# PROCESSOR.net
KiCad netlist of a schematic drawn in Altium Designer
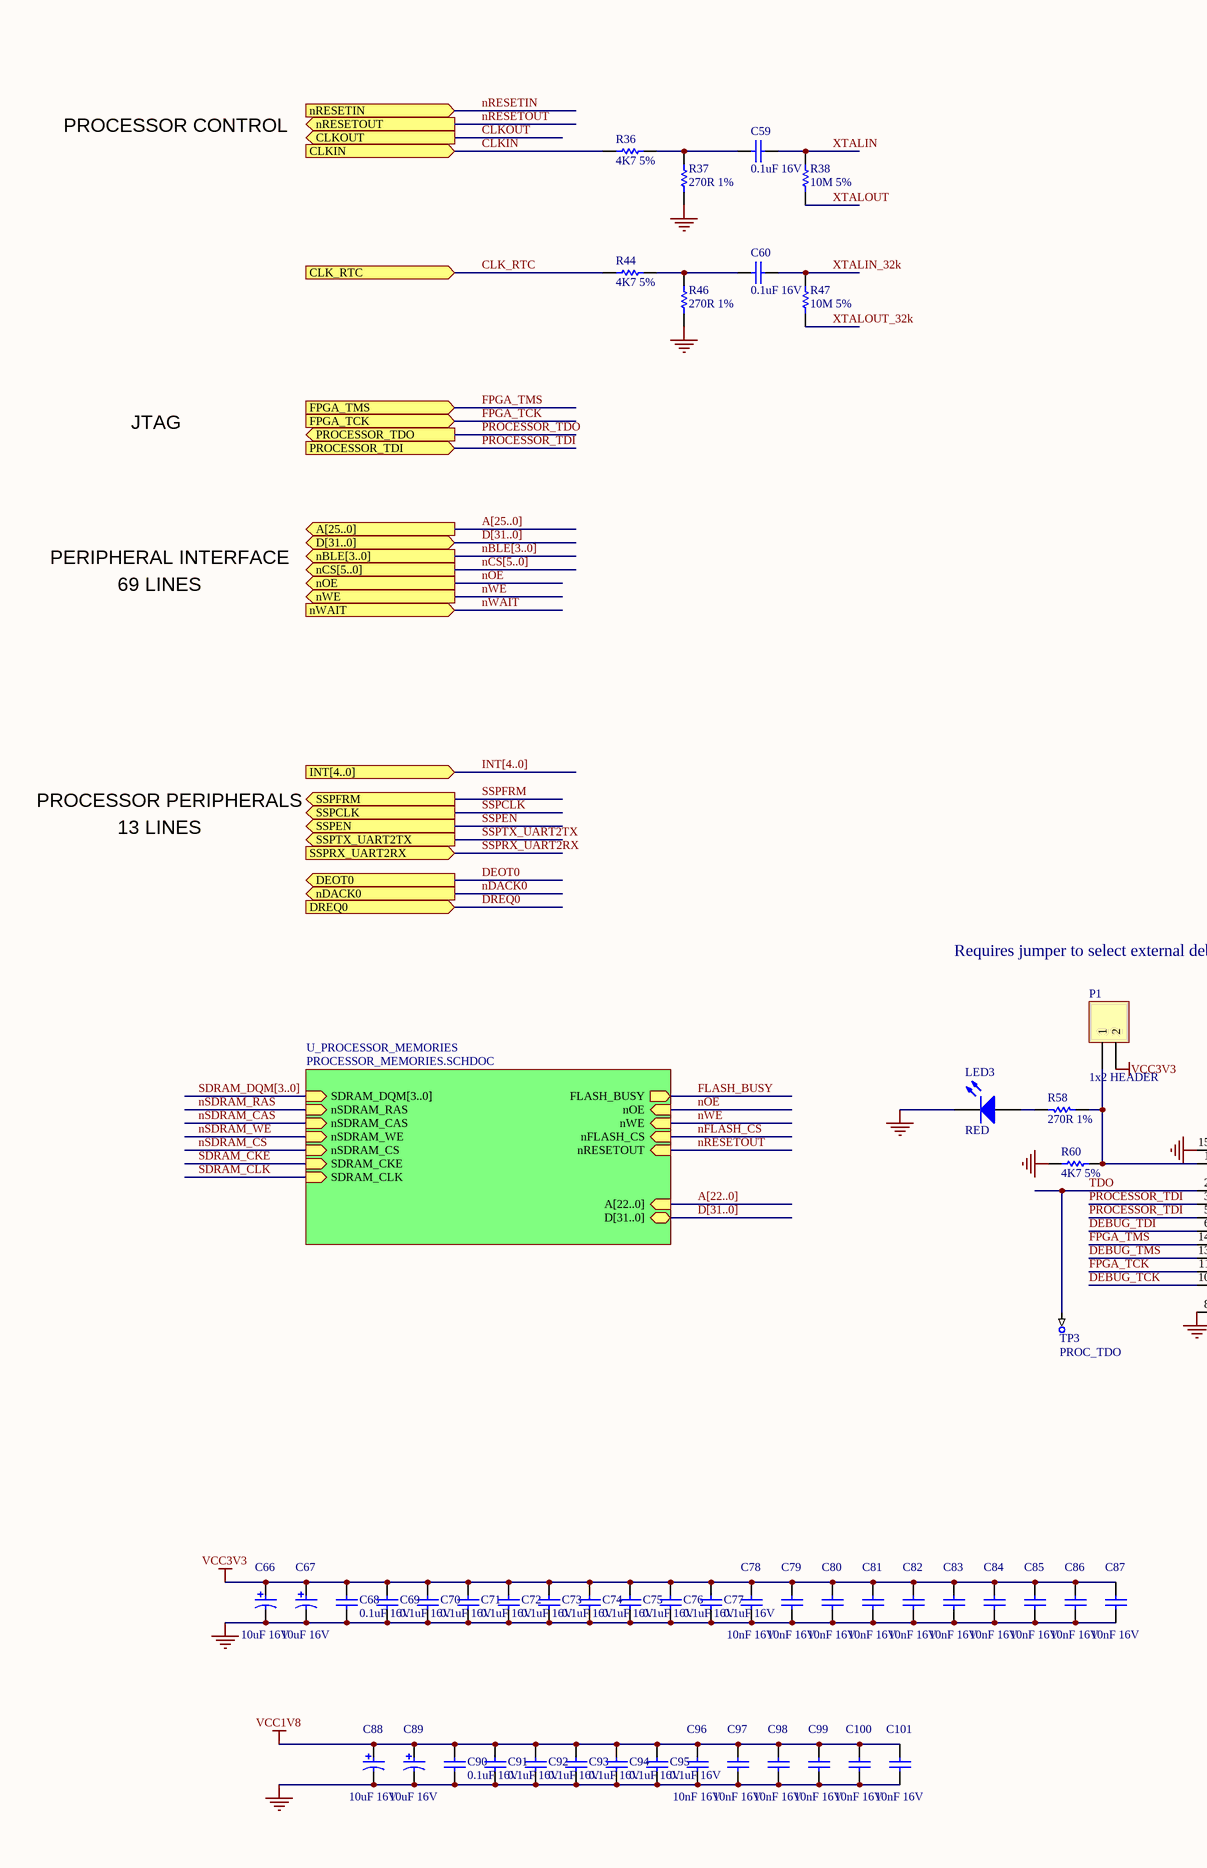
[diagram p0: PROCESSOR.SCHDOC, left]
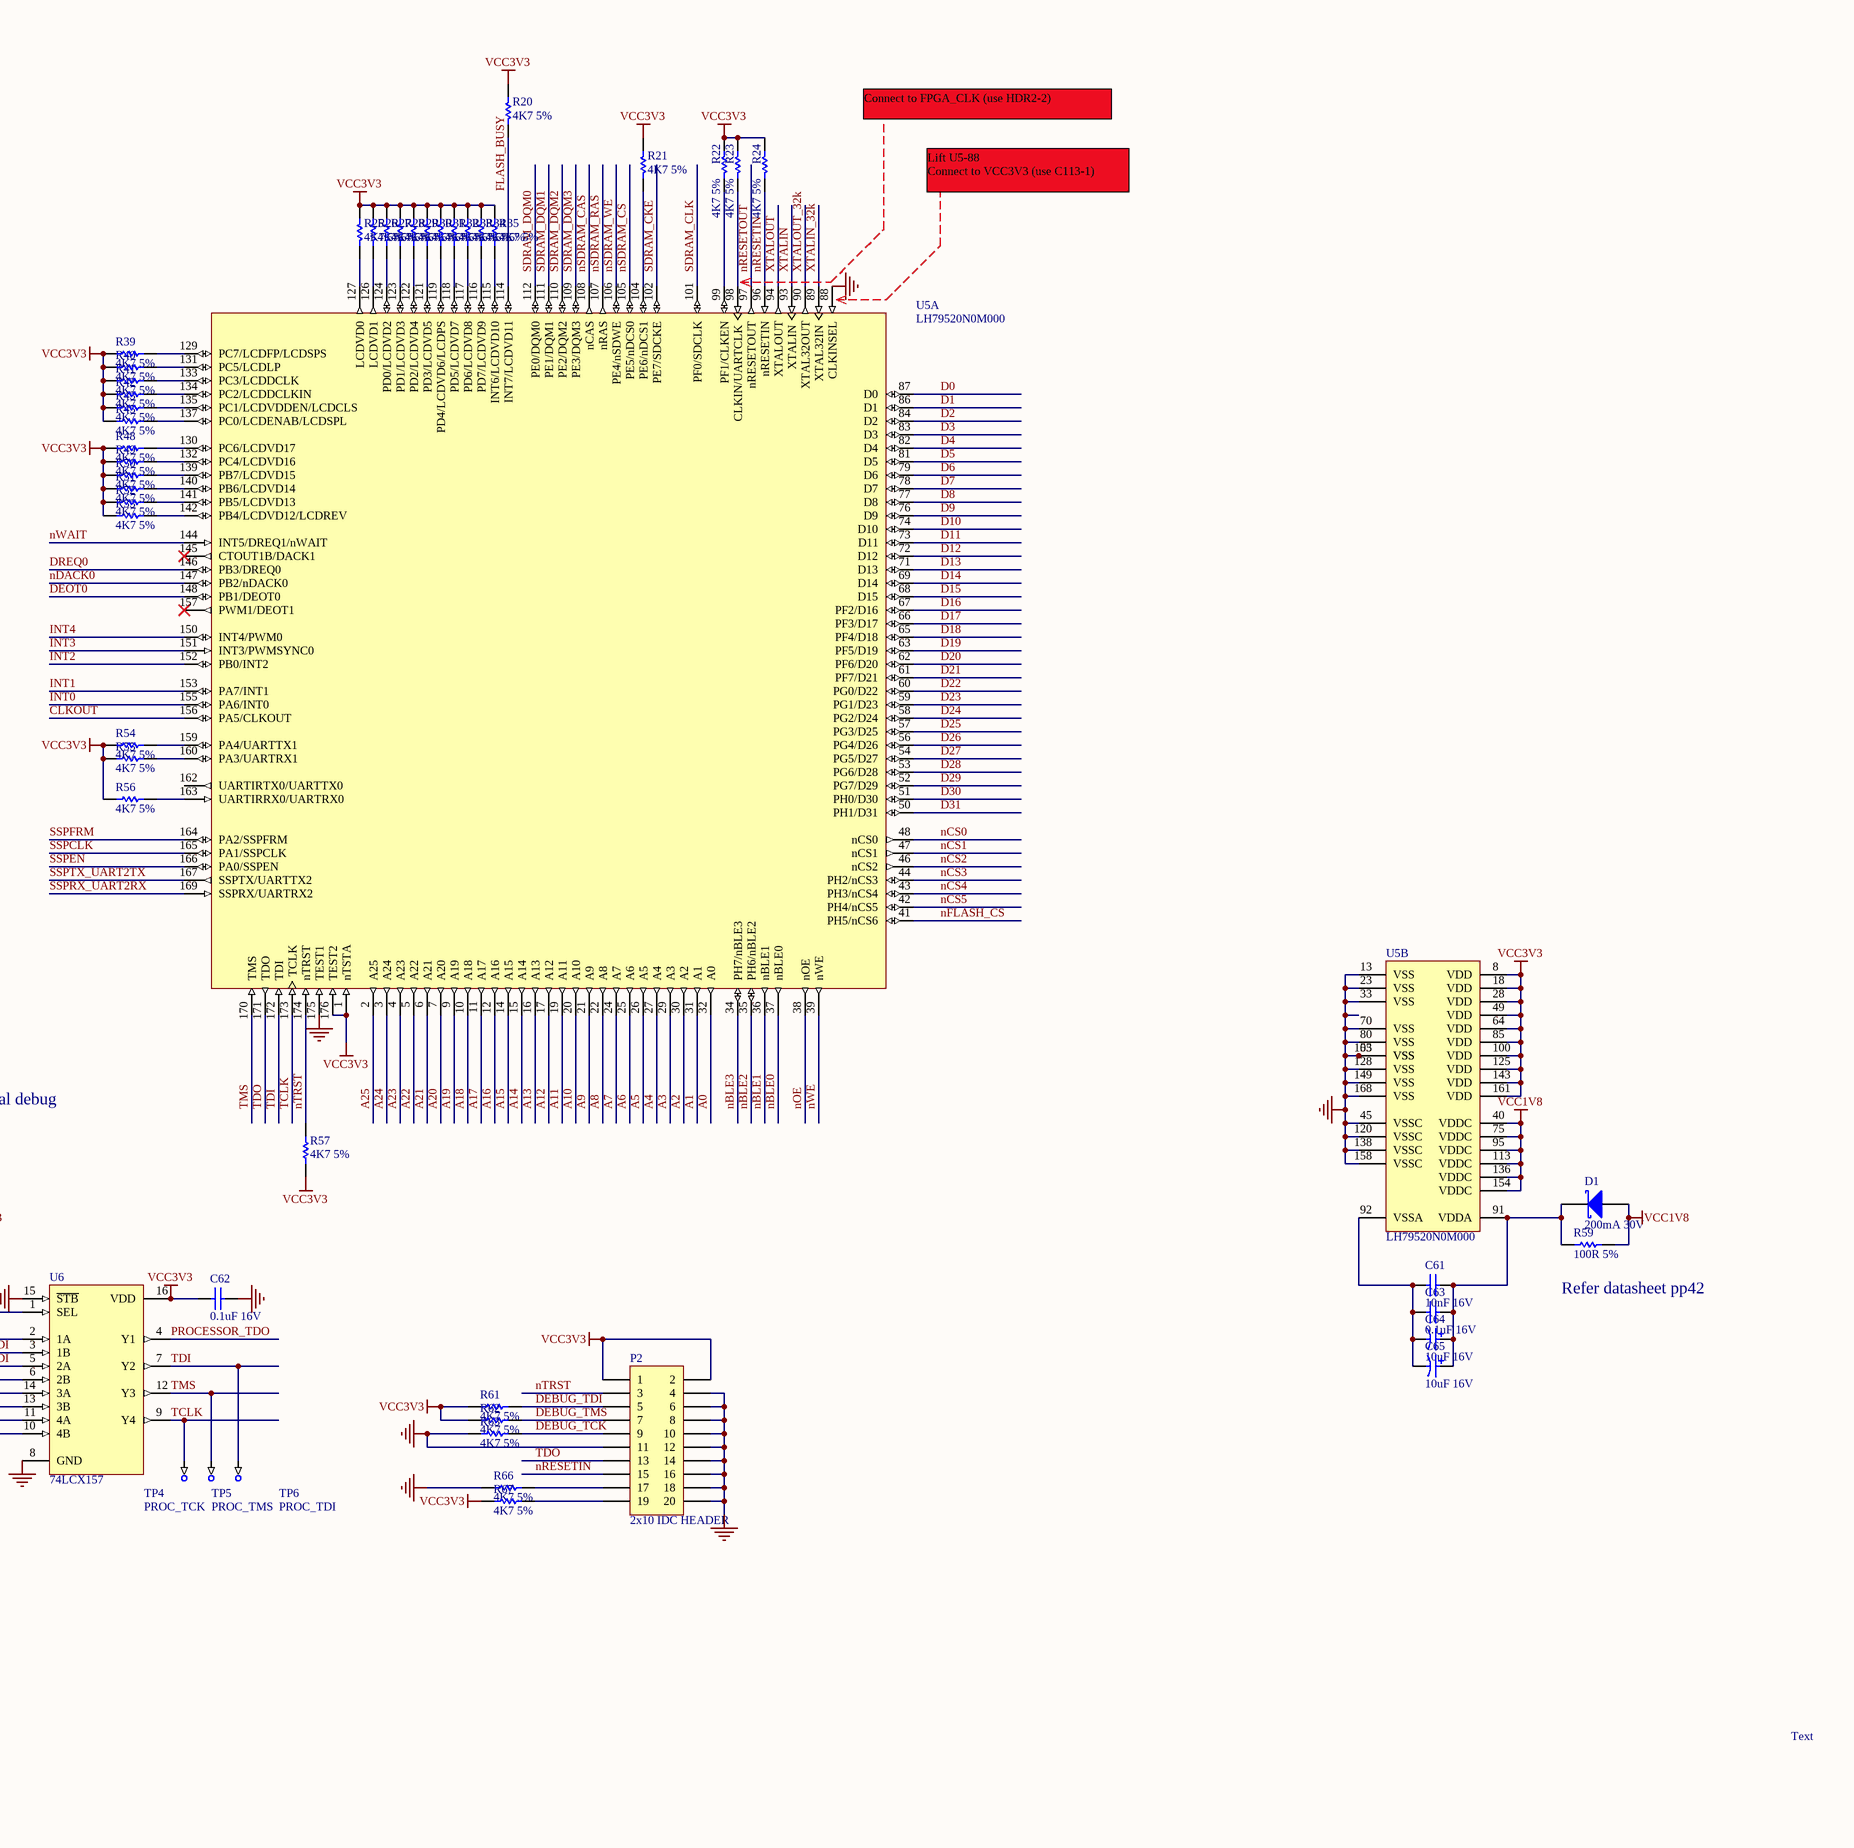
[diagram p1: PROCESSOR.SCHDOC, right]

(export (version "E")
  (design (tool "Eeschema 10.0.6"))
  (components
    (comp (ref "C59")
      (value "0.1uF 16V")
      (footprint "CAPC1005")
      (description "Capacitor")
      (libsource (lib "Altium Design Library") (part "CAP-NP"))
    )
    (comp (ref "C60")
      (value "0.1uF 16V")
      (footprint "CAPC1005")
      (description "Capacitor")
      (libsource (lib "Altium Design Library") (part "CAP-NP"))
    )
    (comp (ref "C61")
      (value "10nF 16V")
      (footprint "CAPC1005")
      (description "Capacitor")
      (libsource (lib "Altium Design Library") (part "CAP-NP"))
    )
    (comp (ref "C62")
      (value "0.1uF 16V")
      (footprint "CAPC1005")
      (description "Capacitor")
      (libsource (lib "Altium Design Library") (part "CAP-NP"))
    )
    (comp (ref "C63")
      (value "0.1uF 16V")
      (footprint "CAPC1005")
      (description "Capacitor")
      (libsource (lib "Altium Design Library") (part "CAP-NP"))
    )
    (comp (ref "C64")
      (value "10uF 16V")
      (footprint "CAPC3528")
      (description "Polar Capacitor")
      (libsource (lib "Altium Design Library") (part "CAP-P"))
    )
    (comp (ref "C65")
      (value "10uF 16V")
      (footprint "CAPC3528")
      (description "Polar Capacitor")
      (libsource (lib "Altium Design Library") (part "CAP-P"))
    )
    (comp (ref "C66")
      (value "10uF 16V")
      (footprint "CAPC3528")
      (description "Polar Capacitor")
      (libsource (lib "Altium Design Library") (part "CAP-P"))
    )
    (comp (ref "C67")
      (value "10uF 16V")
      (footprint "CAPC3528")
      (description "Polar Capacitor")
      (libsource (lib "Altium Design Library") (part "CAP-P"))
    )
    (comp (ref "C68")
      (value "0.1uF 16V")
      (footprint "CAPC1005")
      (description "Capacitor")
      (libsource (lib "Altium Design Library") (part "CAP-NP"))
    )
    (comp (ref "C69")
      (value "0.1uF 16V")
      (footprint "CAPC1005")
      (description "Capacitor")
      (libsource (lib "Altium Design Library") (part "CAP-NP"))
    )
    (comp (ref "C70")
      (value "0.1uF 16V")
      (footprint "CAPC1005")
      (description "Capacitor")
      (libsource (lib "Altium Design Library") (part "CAP-NP"))
    )
    (comp (ref "C71")
      (value "0.1uF 16V")
      (footprint "CAPC1005")
      (description "Capacitor")
      (libsource (lib "Altium Design Library") (part "CAP-NP"))
    )
    (comp (ref "C72")
      (value "0.1uF 16V")
      (footprint "CAPC1005")
      (description "Capacitor")
      (libsource (lib "Altium Design Library") (part "CAP-NP"))
    )
    (comp (ref "C73")
      (value "0.1uF 16V")
      (footprint "CAPC1005")
      (description "Capacitor")
      (libsource (lib "Altium Design Library") (part "CAP-NP"))
    )
    (comp (ref "C74")
      (value "0.1uF 16V")
      (footprint "CAPC1005")
      (description "Capacitor")
      (libsource (lib "Altium Design Library") (part "CAP-NP"))
    )
    (comp (ref "C75")
      (value "0.1uF 16V")
      (footprint "CAPC1005")
      (description "Capacitor")
      (libsource (lib "Altium Design Library") (part "CAP-NP"))
    )
    (comp (ref "C76")
      (value "0.1uF 16V")
      (footprint "CAPC1005")
      (description "Capacitor")
      (libsource (lib "Altium Design Library") (part "CAP-NP"))
    )
    (comp (ref "C77")
      (value "0.1uF 16V")
      (footprint "CAPC1005")
      (description "Capacitor")
      (libsource (lib "Altium Design Library") (part "CAP-NP"))
    )
    (comp (ref "C78")
      (value "10nF 16V")
      (footprint "CAPC1005")
      (description "Capacitor")
      (libsource (lib "Altium Design Library") (part "CAP-NP"))
    )
    (comp (ref "C79")
      (value "10nF 16V")
      (footprint "CAPC1005")
      (description "Capacitor")
      (libsource (lib "Altium Design Library") (part "CAP-NP"))
    )
    (comp (ref "C80")
      (value "10nF 16V")
      (footprint "CAPC1005")
      (description "Capacitor")
      (libsource (lib "Altium Design Library") (part "CAP-NP"))
    )
    (comp (ref "C81")
      (value "10nF 16V")
      (footprint "CAPC1005")
      (description "Capacitor")
      (libsource (lib "Altium Design Library") (part "CAP-NP"))
    )
    (comp (ref "C82")
      (value "10nF 16V")
      (footprint "CAPC1005")
      (description "Capacitor")
      (libsource (lib "Altium Design Library") (part "CAP-NP"))
    )
    (comp (ref "C83")
      (value "10nF 16V")
      (footprint "CAPC1005")
      (description "Capacitor")
      (libsource (lib "Altium Design Library") (part "CAP-NP"))
    )
    (comp (ref "C84")
      (value "10nF 16V")
      (footprint "CAPC1005")
      (description "Capacitor")
      (libsource (lib "Altium Design Library") (part "CAP-NP"))
    )
    (comp (ref "C85")
      (value "10nF 16V")
      (footprint "CAPC1005")
      (description "Capacitor")
      (libsource (lib "Altium Design Library") (part "CAP-NP"))
    )
    (comp (ref "C86")
      (value "10nF 16V")
      (footprint "CAPC1005")
      (description "Capacitor")
      (libsource (lib "Altium Design Library") (part "CAP-NP"))
    )
    (comp (ref "C87")
      (value "10nF 16V")
      (footprint "CAPC1005")
      (description "Capacitor")
      (libsource (lib "Altium Design Library") (part "CAP-NP"))
    )
    (comp (ref "C88")
      (value "10uF 16V")
      (footprint "CAPC3528")
      (description "Polar Capacitor")
      (libsource (lib "Altium Design Library") (part "CAP-P"))
    )
    (comp (ref "C89")
      (value "10uF 16V")
      (footprint "CAPC3528")
      (description "Polar Capacitor")
      (libsource (lib "Altium Design Library") (part "CAP-P"))
    )
    (comp (ref "C90")
      (value "0.1uF 16V")
      (footprint "CAPC1005")
      (description "Capacitor")
      (libsource (lib "Altium Design Library") (part "CAP-NP"))
    )
    (comp (ref "C91")
      (value "0.1uF 16V")
      (footprint "CAPC1005")
      (description "Capacitor")
      (libsource (lib "Altium Design Library") (part "CAP-NP"))
    )
    (comp (ref "C92")
      (value "0.1uF 16V")
      (footprint "CAPC1005")
      (description "Capacitor")
      (libsource (lib "Altium Design Library") (part "CAP-NP"))
    )
    (comp (ref "C93")
      (value "0.1uF 16V")
      (footprint "CAPC1005")
      (description "Capacitor")
      (libsource (lib "Altium Design Library") (part "CAP-NP"))
    )
    (comp (ref "C94")
      (value "0.1uF 16V")
      (footprint "CAPC1005")
      (description "Capacitor")
      (libsource (lib "Altium Design Library") (part "CAP-NP"))
    )
    (comp (ref "C95")
      (value "0.1uF 16V")
      (footprint "CAPC1005")
      (description "Capacitor")
      (libsource (lib "Altium Design Library") (part "CAP-NP"))
    )
    (comp (ref "C96")
      (value "10nF 16V")
      (footprint "CAPC1005")
      (description "Capacitor")
      (libsource (lib "Altium Design Library") (part "CAP-NP"))
    )
    (comp (ref "C97")
      (value "10nF 16V")
      (footprint "CAPC1005")
      (description "Capacitor")
      (libsource (lib "Altium Design Library") (part "CAP-NP"))
    )
    (comp (ref "C98")
      (value "10nF 16V")
      (footprint "CAPC1005")
      (description "Capacitor")
      (libsource (lib "Altium Design Library") (part "CAP-NP"))
    )
    (comp (ref "C99")
      (value "10nF 16V")
      (footprint "CAPC1005")
      (description "Capacitor")
      (libsource (lib "Altium Design Library") (part "CAP-NP"))
    )
    (comp (ref "C100")
      (value "10nF 16V")
      (footprint "CAPC1005")
      (description "Capacitor")
      (libsource (lib "Altium Design Library") (part "CAP-NP"))
    )
    (comp (ref "C101")
      (value "10nF 16V")
      (footprint "CAPC1005")
      (description "Capacitor")
      (libsource (lib "Altium Design Library") (part "CAP-NP"))
    )
    (comp (ref "D1")
      (value "200mA 30V")
      (footprint "SOT95P230-3")
      (description "Schottky Barrier Double Diode")
      (libsource (lib "Altium Design Library") (part "DIO-SCHOTTKY-1S-SOT23"))
    )
    (comp (ref "LED3")
      (value "RED")
      (footprint "LED2013")
      (description "Typical GREEN SMD LED Agilent make")
      (libsource (lib "Altium Design Library") (part "DIO-LED-1S"))
    )
    (comp (ref "P1")
      (value "1x2 HEADER")
      (footprint "HDR1X2")
      (description "Header, 2-Pin")
      (libsource (lib "Altium Design Library") (part "CON-HDR-1x2-STR"))
    )
    (comp (ref "P2")
      (value "2x10 IDC HEADER")
      (footprint "IDC2.54-V20D")
      (description "10x2 IDC Male PCB Box Header")
      (libsource (lib "Altium Design Library") (part "CON-IDC-2x10-M-STR"))
    )
    (comp (ref "R20")
      (value "4K7 5%")
      (footprint "RESC1005")
      (description "Resistor")
      (libsource (lib "Altium Design Library") (part "RES"))
    )
    (comp (ref "R21")
      (value "4K7 5%")
      (footprint "RESC1005")
      (description "Resistor")
      (libsource (lib "Altium Design Library") (part "RES"))
    )
    (comp (ref "R22")
      (value "4K7 5%")
      (footprint "RESC1005")
      (description "Resistor")
      (libsource (lib "Altium Design Library") (part "RES"))
    )
    (comp (ref "R23")
      (value "4K7 5%")
      (footprint "RESC1005")
      (description "Resistor")
      (libsource (lib "Altium Design Library") (part "RES"))
    )
    (comp (ref "R24")
      (value "4K7 5%")
      (footprint "RESC1005")
      (description "Resistor")
      (libsource (lib "Altium Design Library") (part "RES"))
    )
    (comp (ref "R25")
      (value "4K7 5%")
      (footprint "RESC1005")
      (description "Resistor")
      (libsource (lib "Altium Design Library") (part "RES"))
    )
    (comp (ref "R26")
      (value "4K7 5%")
      (footprint "RESC1005")
      (description "Resistor")
      (libsource (lib "Altium Design Library") (part "RES"))
    )
    (comp (ref "R27")
      (value "4K7 5%")
      (footprint "RESC1005")
      (description "Resistor")
      (libsource (lib "Altium Design Library") (part "RES"))
    )
    (comp (ref "R28")
      (value "4K7 5%")
      (footprint "RESC1005")
      (description "Resistor")
      (libsource (lib "Altium Design Library") (part "RES"))
    )
    (comp (ref "R29")
      (value "4K7 5%")
      (footprint "RESC1005")
      (description "Resistor")
      (libsource (lib "Altium Design Library") (part "RES"))
    )
    (comp (ref "R30")
      (value "4K7 5%")
      (footprint "RESC1005")
      (description "Resistor")
      (libsource (lib "Altium Design Library") (part "RES"))
    )
    (comp (ref "R31")
      (value "4K7 5%")
      (footprint "RESC1005")
      (description "Resistor")
      (libsource (lib "Altium Design Library") (part "RES"))
    )
    (comp (ref "R32")
      (value "4K7 5%")
      (footprint "RESC1005")
      (description "Resistor")
      (libsource (lib "Altium Design Library") (part "RES"))
    )
    (comp (ref "R33")
      (value "4K7 5%")
      (footprint "RESC1005")
      (description "Resistor")
      (libsource (lib "Altium Design Library") (part "RES"))
    )
    (comp (ref "R34")
      (value "4K7 5%")
      (footprint "RESC1005")
      (description "Resistor")
      (libsource (lib "Altium Design Library") (part "RES"))
    )
    (comp (ref "R35")
      (value "4K7 5%")
      (footprint "RESC1005")
      (description "Resistor")
      (libsource (lib "Altium Design Library") (part "RES"))
    )
    (comp (ref "R36")
      (value "4K7 5%")
      (footprint "RESC1005")
      (description "Resistor")
      (libsource (lib "Altium Design Library") (part "RES"))
    )
    (comp (ref "R37")
      (value "270R 1%")
      (footprint "RESC2012")
      (description "Resistor")
      (libsource (lib "Altium Design Library") (part "RES"))
    )
    (comp (ref "R38")
      (value "10M 5%")
      (footprint "RESC2012")
      (description "Resistor")
      (libsource (lib "Altium Design Library") (part "RES"))
    )
    (comp (ref "R39")
      (value "4K7 5%")
      (footprint "RESC1005")
      (description "Resistor")
      (libsource (lib "Altium Design Library") (part "RES"))
    )
    (comp (ref "R40")
      (value "4K7 5%")
      (footprint "RESC1005")
      (description "Resistor")
      (libsource (lib "Altium Design Library") (part "RES"))
    )
    (comp (ref "R41")
      (value "4K7 5%")
      (footprint "RESC1005")
      (description "Resistor")
      (libsource (lib "Altium Design Library") (part "RES"))
    )
    (comp (ref "R42")
      (value "4K7 5%")
      (footprint "RESC1005")
      (description "Resistor")
      (libsource (lib "Altium Design Library") (part "RES"))
    )
    (comp (ref "R43")
      (value "4K7 5%")
      (footprint "RESC1005")
      (description "Resistor")
      (libsource (lib "Altium Design Library") (part "RES"))
    )
    (comp (ref "R44")
      (value "4K7 5%")
      (footprint "RESC1005")
      (description "Resistor")
      (libsource (lib "Altium Design Library") (part "RES"))
    )
    (comp (ref "R45")
      (value "4K7 5%")
      (footprint "RESC1005")
      (description "Resistor")
      (libsource (lib "Altium Design Library") (part "RES"))
    )
    (comp (ref "R46")
      (value "270R 1%")
      (footprint "RESC2012")
      (description "Resistor")
      (libsource (lib "Altium Design Library") (part "RES"))
    )
    (comp (ref "R47")
      (value "10M 5%")
      (footprint "RESC2012")
      (description "Resistor")
      (libsource (lib "Altium Design Library") (part "RES"))
    )
    (comp (ref "R48")
      (value "4K7 5%")
      (footprint "RESC1005")
      (description "Resistor")
      (libsource (lib "Altium Design Library") (part "RES"))
    )
    (comp (ref "R49")
      (value "4K7 5%")
      (footprint "RESC1005")
      (description "Resistor")
      (libsource (lib "Altium Design Library") (part "RES"))
    )
    (comp (ref "R50")
      (value "4K7 5%")
      (footprint "RESC1005")
      (description "Resistor")
      (libsource (lib "Altium Design Library") (part "RES"))
    )
    (comp (ref "R51")
      (value "4K7 5%")
      (footprint "RESC1005")
      (description "Resistor")
      (libsource (lib "Altium Design Library") (part "RES"))
    )
    (comp (ref "R52")
      (value "4K7 5%")
      (footprint "RESC1005")
      (description "Resistor")
      (libsource (lib "Altium Design Library") (part "RES"))
    )
    (comp (ref "R53")
      (value "4K7 5%")
      (footprint "RESC1005")
      (description "Resistor")
      (libsource (lib "Altium Design Library") (part "RES"))
    )
    (comp (ref "R54")
      (value "4K7 5%")
      (footprint "RESC1005")
      (description "Resistor")
      (libsource (lib "Altium Design Library") (part "RES"))
    )
    (comp (ref "R55")
      (value "4K7 5%")
      (footprint "RESC1005")
      (description "Resistor")
      (libsource (lib "Altium Design Library") (part "RES"))
    )
    (comp (ref "R56")
      (value "4K7 5%")
      (footprint "RESC1005")
      (description "Resistor")
      (libsource (lib "Altium Design Library") (part "RES"))
    )
    (comp (ref "R57")
      (value "4K7 5%")
      (footprint "RESC1005")
      (description "Resistor")
      (libsource (lib "Altium Design Library") (part "RES"))
    )
    (comp (ref "R58")
      (value "270R 1%")
      (footprint "RESC2012")
      (description "Resistor")
      (libsource (lib "Altium Design Library") (part "RES"))
    )
    (comp (ref "R59")
      (value "100R 5%")
      (footprint "RESC2012")
      (description "Resistor")
      (libsource (lib "Altium Design Library") (part "RES"))
    )
    (comp (ref "R60")
      (value "4K7 5%")
      (footprint "RESC1005")
      (description "Resistor")
      (libsource (lib "Altium Design Library") (part "RES"))
    )
    (comp (ref "R61")
      (value "4K7 5%")
      (footprint "RESC1005")
      (description "Resistor")
      (libsource (lib "Altium Design Library") (part "RES"))
    )
    (comp (ref "R62")
      (value "4K7 5%")
      (footprint "RESC1005")
      (description "Resistor")
      (libsource (lib "Altium Design Library") (part "RES"))
    )
    (comp (ref "R63")
      (value "4K7 5%")
      (footprint "RESC1005")
      (description "Resistor")
      (libsource (lib "Altium Design Library") (part "RES"))
    )
    (comp (ref "R66")
      (value "4K7 5%")
      (footprint "RESC1005")
      (description "Resistor")
      (libsource (lib "Altium Design Library") (part "RES"))
    )
    (comp (ref "R67")
      (value "4K7 5%")
      (footprint "RESC1005")
      (description "Resistor")
      (libsource (lib "Altium Design Library") (part "RES"))
    )
    (comp (ref "TP3")
      (value "PROC_TDO")
      (footprint "TestPin")
      (libsource (lib "Altium Design Library") (part "TestPin"))
    )
    (comp (ref "TP4")
      (value "PROC_TCK")
      (footprint "TestPin")
      (libsource (lib "Altium Design Library") (part "TestPin"))
    )
    (comp (ref "TP5")
      (value "PROC_TMS")
      (footprint "TestPin")
      (libsource (lib "Altium Design Library") (part "TestPin"))
    )
    (comp (ref "TP6")
      (value "PROC_TDI")
      (footprint "TestPin")
      (libsource (lib "Altium Design Library") (part "TestPin"))
    )
    (comp (ref "U5")
      (value "LH79520N0M000")
      (footprint "QFP40P2000X2000-176")
      (libsource (lib "Altium Design Library") (part "LH79520N0M000"))
    )
    (comp (ref "U6")
      (value "74LCX157")
      (footprint "TSOP65P638-16")
      (description "Quad 2-Input Multiplexer")
      (libsource (lib "Altium Design Library") (part "74LCX157-TSOP16"))
    )
  )
  (nets
    (net (code "1") (name "/A0") (class "Default")
      (node (ref "U5") (pin "32") (pinfunction "A0_32") (pintype "output"))
    )
    (net (code "2") (name "/A1") (class "Default")
      (node (ref "U5") (pin "31") (pinfunction "A1_31") (pintype "output"))
    )
    (net (code "3") (name "/A2") (class "Default")
      (node (ref "U5") (pin "30") (pinfunction "A2_30") (pintype "output"))
    )
    (net (code "4") (name "/A3") (class "Default")
      (node (ref "U5") (pin "29") (pinfunction "A3_29") (pintype "output"))
    )
    (net (code "5") (name "/A4") (class "Default")
      (node (ref "U5") (pin "27") (pinfunction "A4_27") (pintype "output"))
    )
    (net (code "6") (name "/A5") (class "Default")
      (node (ref "U5") (pin "26") (pinfunction "A5_26") (pintype "output"))
    )
    (net (code "7") (name "/A6") (class "Default")
      (node (ref "U5") (pin "25") (pinfunction "A6_25") (pintype "output"))
    )
    (net (code "8") (name "/A7") (class "Default")
      (node (ref "U5") (pin "24") (pinfunction "A7_24") (pintype "output"))
    )
    (net (code "9") (name "/A8") (class "Default")
      (node (ref "U5") (pin "22") (pinfunction "A8_22") (pintype "output"))
    )
    (net (code "10") (name "/A9") (class "Default")
      (node (ref "U5") (pin "21") (pinfunction "A9_21") (pintype "output"))
    )
    (net (code "11") (name "/A10") (class "Default")
      (node (ref "U5") (pin "20") (pinfunction "A10_20") (pintype "output"))
    )
    (net (code "12") (name "/A11") (class "Default")
      (node (ref "U5") (pin "19") (pinfunction "A11_19") (pintype "output"))
    )
    (net (code "13") (name "/A12") (class "Default")
      (node (ref "U5") (pin "17") (pinfunction "A12_17") (pintype "output"))
    )
    (net (code "14") (name "/A13") (class "Default")
      (node (ref "U5") (pin "16") (pinfunction "A13_16") (pintype "output"))
    )
    (net (code "15") (name "/A14") (class "Default")
      (node (ref "U5") (pin "15") (pinfunction "A14_15") (pintype "output"))
    )
    (net (code "16") (name "/A15") (class "Default")
      (node (ref "U5") (pin "14") (pinfunction "A15_14") (pintype "output"))
    )
    (net (code "17") (name "/A16") (class "Default")
      (node (ref "U5") (pin "12") (pinfunction "A16_12") (pintype "output"))
    )
    (net (code "18") (name "/A17") (class "Default")
      (node (ref "U5") (pin "11") (pinfunction "A17_11") (pintype "output"))
    )
    (net (code "19") (name "/A18") (class "Default")
      (node (ref "U5") (pin "10") (pinfunction "A18_10") (pintype "output"))
    )
    (net (code "20") (name "/A19") (class "Default")
      (node (ref "U5") (pin "9") (pinfunction "A19_9") (pintype "output"))
    )
    (net (code "21") (name "/A20") (class "Default")
      (node (ref "U5") (pin "7") (pinfunction "A20_7") (pintype "output"))
    )
    (net (code "22") (name "/A21") (class "Default")
      (node (ref "U5") (pin "6") (pinfunction "A21_6") (pintype "output"))
    )
    (net (code "23") (name "/A22") (class "Default")
      (node (ref "U5") (pin "5") (pinfunction "A22_5") (pintype "output"))
    )
    (net (code "24") (name "/A23") (class "Default")
      (node (ref "U5") (pin "4") (pinfunction "A23_4") (pintype "output"))
    )
    (net (code "25") (name "/A24") (class "Default")
      (node (ref "U5") (pin "3") (pinfunction "A24_3") (pintype "output"))
    )
    (net (code "26") (name "/A25") (class "Default")
      (node (ref "U5") (pin "2") (pinfunction "A25_2") (pintype "output"))
    )
    (net (code "29") (name "/CLKIN") (class "Default")
      (node (ref "R36") (pin "2") (pinfunction "2_2") (pintype "passive"))
    )
    (net (code "30") (name "/CLKOUT") (class "Default")
      (node (ref "U5") (pin "156") (pinfunction "PA5/CLKOUT_156") (pintype "bidirectional"))
    )
    (net (code "31") (name "/CLK_RTC") (class "Default")
      (node (ref "R44") (pin "2") (pinfunction "2_2") (pintype "passive"))
    )
    (net (code "32") (name "/D0") (class "Default")
      (node (ref "U5") (pin "87") (pinfunction "D0_87") (pintype "bidirectional"))
    )
    (net (code "33") (name "/D1") (class "Default")
      (node (ref "U5") (pin "86") (pinfunction "D1_86") (pintype "bidirectional"))
    )
    (net (code "34") (name "/D2") (class "Default")
      (node (ref "U5") (pin "84") (pinfunction "D2_84") (pintype "bidirectional"))
    )
    (net (code "35") (name "/D3") (class "Default")
      (node (ref "U5") (pin "83") (pinfunction "D3_83") (pintype "bidirectional"))
    )
    (net (code "36") (name "/D4") (class "Default")
      (node (ref "U5") (pin "82") (pinfunction "D4_82") (pintype "bidirectional"))
    )
    (net (code "37") (name "/D5") (class "Default")
      (node (ref "U5") (pin "81") (pinfunction "D5_81") (pintype "bidirectional"))
    )
    (net (code "38") (name "/D6") (class "Default")
      (node (ref "U5") (pin "79") (pinfunction "D6_79") (pintype "bidirectional"))
    )
    (net (code "39") (name "/D7") (class "Default")
      (node (ref "U5") (pin "78") (pinfunction "D7_78") (pintype "bidirectional"))
    )
    (net (code "40") (name "/D8") (class "Default")
      (node (ref "U5") (pin "77") (pinfunction "D8_77") (pintype "bidirectional"))
    )
    (net (code "41") (name "/D9") (class "Default")
      (node (ref "U5") (pin "76") (pinfunction "D9_76") (pintype "bidirectional"))
    )
    (net (code "42") (name "/D10") (class "Default")
      (node (ref "U5") (pin "74") (pinfunction "D10_74") (pintype "bidirectional"))
    )
    (net (code "43") (name "/D11") (class "Default")
      (node (ref "U5") (pin "73") (pinfunction "D11_73") (pintype "bidirectional"))
    )
    (net (code "44") (name "/D12") (class "Default")
      (node (ref "U5") (pin "72") (pinfunction "D12_72") (pintype "bidirectional"))
    )
    (net (code "45") (name "/D13") (class "Default")
      (node (ref "U5") (pin "71") (pinfunction "D13_71") (pintype "bidirectional"))
    )
    (net (code "46") (name "/D14") (class "Default")
      (node (ref "U5") (pin "69") (pinfunction "D14_69") (pintype "bidirectional"))
    )
    (net (code "47") (name "/D15") (class "Default")
      (node (ref "U5") (pin "68") (pinfunction "D15_68") (pintype "bidirectional"))
    )
    (net (code "48") (name "/D16") (class "Default")
      (node (ref "U5") (pin "67") (pinfunction "PF2/D16_67") (pintype "bidirectional"))
    )
    (net (code "49") (name "/D17") (class "Default")
      (node (ref "U5") (pin "66") (pinfunction "PF3/D17_66") (pintype "bidirectional"))
    )
    (net (code "50") (name "/D18") (class "Default")
      (node (ref "U5") (pin "65") (pinfunction "PF4/D18_65") (pintype "bidirectional"))
    )
    (net (code "51") (name "/D19") (class "Default")
      (node (ref "U5") (pin "63") (pinfunction "PF5/D19_63") (pintype "bidirectional"))
    )
    (net (code "52") (name "/D20") (class "Default")
      (node (ref "U5") (pin "62") (pinfunction "PF6/D20_62") (pintype "bidirectional"))
    )
    (net (code "53") (name "/D21") (class "Default")
      (node (ref "U5") (pin "61") (pinfunction "PF7/D21_61") (pintype "bidirectional"))
    )
    (net (code "54") (name "/D22") (class "Default")
      (node (ref "U5") (pin "60") (pinfunction "PG0/D22_60") (pintype "bidirectional"))
    )
    (net (code "55") (name "/D23") (class "Default")
      (node (ref "U5") (pin "59") (pinfunction "PG1/D23_59") (pintype "bidirectional"))
    )
    (net (code "56") (name "/D24") (class "Default")
      (node (ref "U5") (pin "58") (pinfunction "PG2/D24_58") (pintype "bidirectional"))
    )
    (net (code "57") (name "/D25") (class "Default")
      (node (ref "U5") (pin "57") (pinfunction "PG3/D25_57") (pintype "bidirectional"))
    )
    (net (code "58") (name "/D26") (class "Default")
      (node (ref "U5") (pin "56") (pinfunction "PG4/D26_56") (pintype "bidirectional"))
    )
    (net (code "59") (name "/D27") (class "Default")
      (node (ref "U5") (pin "54") (pinfunction "PG5/D27_54") (pintype "bidirectional"))
    )
    (net (code "60") (name "/D28") (class "Default")
      (node (ref "U5") (pin "53") (pinfunction "PG6/D28_53") (pintype "bidirectional"))
    )
    (net (code "61") (name "/D29") (class "Default")
      (node (ref "U5") (pin "52") (pinfunction "PG7/D29_52") (pintype "bidirectional"))
    )
    (net (code "62") (name "/D30") (class "Default")
      (node (ref "U5") (pin "51") (pinfunction "PH0/D30_51") (pintype "bidirectional"))
    )
    (net (code "63") (name "/D31") (class "Default")
      (node (ref "U5") (pin "50") (pinfunction "PH1/D31_50") (pintype "bidirectional"))
    )
    (net (code "64") (name "/DEBUG_TCK") (class "Default")
      (node (ref "P2") (pin "9") (pinfunction "9_9") (pintype "passive"))
      (node (ref "R63") (pin "2") (pinfunction "2_2") (pintype "passive"))
      (node (ref "U6") (pin "10") (pinfunction "4B_10") (pintype "input"))
    )
    (net (code "65") (name "/DEBUG_TDI") (class "Default")
      (node (ref "P2") (pin "5") (pinfunction "5_5") (pintype "passive"))
      (node (ref "R61") (pin "2") (pinfunction "2_2") (pintype "passive"))
      (node (ref "U6") (pin "6") (pinfunction "2B_6") (pintype "input"))
    )
    (net (code "66") (name "/DEBUG_TMS") (class "Default")
      (node (ref "P2") (pin "7") (pinfunction "7_7") (pintype "passive"))
      (node (ref "R62") (pin "2") (pinfunction "2_2") (pintype "passive"))
      (node (ref "U6") (pin "13") (pinfunction "3B_13") (pintype "input"))
    )
    (net (code "67") (name "/DEOT0") (class "Default")
      (node (ref "U5") (pin "148") (pinfunction "PB1/DEOT0_148") (pintype "bidirectional"))
    )
    (net (code "68") (name "/DREQ0") (class "Default")
      (node (ref "U5") (pin "146") (pinfunction "PB3/DREQ0_146") (pintype "bidirectional"))
    )
    (net (code "70") (name "/FLASH_BUSY") (class "Default")
      (node (ref "R20") (pin "1") (pinfunction "1_1") (pintype "passive"))
      (node (ref "U5") (pin "114") (pinfunction "INT7/LCDVD11_114") (pintype "bidirectional"))
    )
    (net (code "71") (name "/FPGA_TCK") (class "Default")
      (node (ref "U6") (pin "11") (pinfunction "4A_11") (pintype "input"))
    )
    (net (code "72") (name "/FPGA_TMS") (class "Default")
      (node (ref "U6") (pin "14") (pinfunction "3A_14") (pintype "input"))
    )
    (net (code "73") (name "/INT0") (class "Default")
      (node (ref "U5") (pin "155") (pinfunction "PA6/INT0_155") (pintype "bidirectional"))
    )
    (net (code "74") (name "/INT1") (class "Default")
      (node (ref "U5") (pin "153") (pinfunction "PA7/INT1_153") (pintype "bidirectional"))
    )
    (net (code "75") (name "/INT2") (class "Default")
      (node (ref "U5") (pin "152") (pinfunction "PB0/INT2_152") (pintype "bidirectional"))
    )
    (net (code "76") (name "/INT3") (class "Default")
      (node (ref "U5") (pin "151") (pinfunction "INT3/PWMSYNC0_151") (pintype "input"))
    )
    (net (code "77") (name "/INT4") (class "Default")
      (node (ref "U5") (pin "150") (pinfunction "INT4/PWM0_150") (pintype "bidirectional"))
    )
    (net (code "79") (name "/PROCESSOR_TDI") (class "Default")
      (node (ref "U6") (pin "3") (pinfunction "1B_3") (pintype "input"))
      (node (ref "U6") (pin "5") (pinfunction "2A_5") (pintype "input"))
    )
    (net (code "80") (name "/PROCESSOR_TDO") (class "Default")
      (node (ref "U6") (pin "4") (pinfunction "Y1_4") (pintype "output"))
    )
    (net (code "81") (name "/SDRAM_CKE") (class "Default")
      (node (ref "U5") (pin "102") (pinfunction "PE7/SDCKE_102") (pintype "bidirectional"))
    )
    (net (code "82") (name "/SDRAM_CLK") (class "Default")
      (node (ref "U5") (pin "101") (pinfunction "PF0/SDCLK_101") (pintype "bidirectional"))
    )
    (net (code "83") (name "/SDRAM_DQM0") (class "Default")
      (node (ref "U5") (pin "112") (pinfunction "PE0/DQM0_112") (pintype "bidirectional"))
    )
    (net (code "84") (name "/SDRAM_DQM1") (class "Default")
      (node (ref "U5") (pin "111") (pinfunction "PE1/DQM1_111") (pintype "bidirectional"))
    )
    (net (code "85") (name "/SDRAM_DQM2") (class "Default")
      (node (ref "U5") (pin "110") (pinfunction "PE2/DQM2_110") (pintype "bidirectional"))
    )
    (net (code "86") (name "/SDRAM_DQM3") (class "Default")
      (node (ref "U5") (pin "109") (pinfunction "PE3/DQM3_109") (pintype "bidirectional"))
    )
    (net (code "88") (name "/SSPCLK") (class "Default")
      (node (ref "U5") (pin "165") (pinfunction "PA1/SSPCLK_165") (pintype "bidirectional"))
    )
    (net (code "89") (name "/SSPEN") (class "Default")
      (node (ref "U5") (pin "166") (pinfunction "PA0/SSPEN_166") (pintype "bidirectional"))
    )
    (net (code "90") (name "/SSPFRM") (class "Default")
      (node (ref "U5") (pin "164") (pinfunction "PA2/SSPFRM_164") (pintype "bidirectional"))
    )
    (net (code "91") (name "/SSPRX_UART2RX") (class "Default")
      (node (ref "U5") (pin "169") (pinfunction "SSPRX/UARTRX2_169") (pintype "input"))
    )
    (net (code "92") (name "/SSPTX_UART2TX") (class "Default")
      (node (ref "U5") (pin "167") (pinfunction "SSPTX/UARTTX2_167") (pintype "output"))
    )
    (net (code "93") (name "/TCLK") (class "Default")
      (node (ref "TP4") (pin "1") (pinfunction "1_1") (pintype "input"))
      (node (ref "U5") (pin "173") (pinfunction "TCLK_173") (pintype "input"))
      (node (ref "U6") (pin "9") (pinfunction "Y4_9") (pintype "output"))
    )
    (net (code "94") (name "/TDI") (class "Default")
      (node (ref "TP6") (pin "1") (pinfunction "1_1") (pintype "input"))
      (node (ref "U5") (pin "172") (pinfunction "TDI_172") (pintype "input"))
      (node (ref "U6") (pin "7") (pinfunction "Y2_7") (pintype "output"))
    )
    (net (code "95") (name "/TDO") (class "Default")
      (node (ref "P2") (pin "13") (pinfunction "13_13") (pintype "passive"))
      (node (ref "TP3") (pin "1") (pinfunction "1_1") (pintype "input"))
      (node (ref "U5") (pin "171") (pinfunction "TDO_171") (pintype "output"))
      (node (ref "U6") (pin "2") (pinfunction "1A_2") (pintype "input"))
    )
    (net (code "96") (name "/TMS") (class "Default")
      (node (ref "TP5") (pin "1") (pinfunction "1_1") (pintype "input"))
      (node (ref "U5") (pin "170") (pinfunction "TMS_170") (pintype "input"))
      (node (ref "U6") (pin "12") (pinfunction "Y3_12") (pintype "output"))
    )
    (net (code "97") (name "/XTALIN") (class "Default")
      (node (ref "C59") (pin "2") (pinfunction "2_2") (pintype "passive"))
      (node (ref "R38") (pin "1") (pinfunction "1_1") (pintype "passive"))
      (node (ref "U5") (pin "93") (pinfunction "XTALIN_93") (pintype "input"))
    )
    (net (code "98") (name "/XTALIN_32k") (class "Default")
      (node (ref "C60") (pin "2") (pinfunction "2_2") (pintype "passive"))
      (node (ref "R47") (pin "1") (pinfunction "1_1") (pintype "passive"))
      (node (ref "U5") (pin "89") (pinfunction "XTAL32IN_89") (pintype "input"))
    )
    (net (code "99") (name "/XTALOUT") (class "Default")
      (node (ref "R38") (pin "2") (pinfunction "2_2") (pintype "passive"))
      (node (ref "U5") (pin "94") (pinfunction "XTALOUT_94") (pintype "output"))
    )
    (net (code "100") (name "/XTALOUT_32k") (class "Default")
      (node (ref "R47") (pin "2") (pinfunction "2_2") (pintype "passive"))
      (node (ref "U5") (pin "90") (pinfunction "XTAL32OUT_90") (pintype "output"))
    )
    (net (code "101") (name "/nBLE0") (class "Default")
      (node (ref "U5") (pin "37") (pinfunction "nBLE0_37") (pintype "output"))
    )
    (net (code "102") (name "/nBLE1") (class "Default")
      (node (ref "U5") (pin "36") (pinfunction "nBLE1_36") (pintype "output"))
    )
    (net (code "103") (name "/nBLE2") (class "Default")
      (node (ref "U5") (pin "35") (pinfunction "PH6/nBLE2_35") (pintype "bidirectional"))
    )
    (net (code "104") (name "/nBLE3") (class "Default")
      (node (ref "U5") (pin "34") (pinfunction "PH7/nBLE3_34") (pintype "bidirectional"))
    )
    (net (code "106") (name "/nCS0") (class "Default")
      (node (ref "U5") (pin "48") (pinfunction "nCS0_48") (pintype "output"))
    )
    (net (code "107") (name "/nCS1") (class "Default")
      (node (ref "U5") (pin "47") (pinfunction "nCS1_47") (pintype "output"))
    )
    (net (code "108") (name "/nCS2") (class "Default")
      (node (ref "U5") (pin "46") (pinfunction "nCS2_46") (pintype "output"))
    )
    (net (code "109") (name "/nCS3") (class "Default")
      (node (ref "U5") (pin "44") (pinfunction "PH2/nCS3_44") (pintype "bidirectional"))
    )
    (net (code "110") (name "/nCS4") (class "Default")
      (node (ref "U5") (pin "43") (pinfunction "PH3/nCS4_43") (pintype "bidirectional"))
    )
    (net (code "111") (name "/nCS5") (class "Default")
      (node (ref "U5") (pin "42") (pinfunction "PH4/nCS5_42") (pintype "bidirectional"))
    )
    (net (code "113") (name "/nDACK0") (class "Default")
      (node (ref "U5") (pin "147") (pinfunction "PB2/nDACK0_147") (pintype "bidirectional"))
    )
    (net (code "114") (name "/nFLASH_CS") (class "Default")
      (node (ref "U5") (pin "41") (pinfunction "PH5/nCS6_41") (pintype "bidirectional"))
    )
    (net (code "115") (name "/nOE") (class "Default")
      (node (ref "U5") (pin "38") (pinfunction "nOE_38") (pintype "output"))
    )
    (net (code "116") (name "/nRESETIN") (class "Default")
      (node (ref "P2") (pin "15") (pinfunction "15_15") (pintype "passive"))
      (node (ref "R24") (pin "1") (pinfunction "1_1") (pintype "passive"))
      (node (ref "U5") (pin "96") (pinfunction "nRESETIN_96") (pintype "input"))
    )
    (net (code "117") (name "/nRESETOUT") (class "Default")
      (node (ref "U5") (pin "97") (pinfunction "nRESETOUT_97") (pintype "output"))
    )
    (net (code "118") (name "/nSDRAM_CAS") (class "Default")
      (node (ref "U5") (pin "108") (pinfunction "nCAS_108") (pintype "output"))
    )
    (net (code "119") (name "/nSDRAM_CS") (class "Default")
      (node (ref "U5") (pin "105") (pinfunction "PE5/nDCS0_105") (pintype "bidirectional"))
    )
    (net (code "120") (name "/nSDRAM_RAS") (class "Default")
      (node (ref "U5") (pin "107") (pinfunction "nRAS_107") (pintype "output"))
    )
    (net (code "121") (name "/nSDRAM_WE") (class "Default")
      (node (ref "U5") (pin "106") (pinfunction "PE4/nSDWE_106") (pintype "bidirectional"))
    )
    (net (code "122") (name "/nTRST") (class "Default")
      (node (ref "P2") (pin "3") (pinfunction "3_3") (pintype "passive"))
      (node (ref "R57") (pin "1") (pinfunction "1_1") (pintype "passive"))
      (node (ref "U5") (pin "174") (pinfunction "nTRST_174") (pintype "input"))
    )
    (net (code "123") (name "/nWAIT") (class "Default")
      (node (ref "U5") (pin "144") (pinfunction "INT5/DREQ1/nWAIT_144") (pintype "input"))
    )
    (net (code "124") (name "/nWE") (class "Default")
      (node (ref "U5") (pin "39") (pinfunction "nWE_39") (pintype "output"))
    )
    (net (code "125") (name "GND") (class "Default")
      (node (ref "C100") (pin "2") (pinfunction "2_2") (pintype "passive"))
      (node (ref "C101") (pin "2") (pinfunction "2_2") (pintype "passive"))
      (node (ref "C62") (pin "2") (pinfunction "2_2") (pintype "passive"))
      (node (ref "C66") (pin "2") (pinfunction "2_2") (pintype "passive"))
      (node (ref "C67") (pin "2") (pinfunction "2_2") (pintype "passive"))
      (node (ref "C68") (pin "2") (pinfunction "2_2") (pintype "passive"))
      (node (ref "C69") (pin "2") (pinfunction "2_2") (pintype "passive"))
      (node (ref "C70") (pin "2") (pinfunction "2_2") (pintype "passive"))
      (node (ref "C71") (pin "2") (pinfunction "2_2") (pintype "passive"))
      (node (ref "C72") (pin "2") (pinfunction "2_2") (pintype "passive"))
      (node (ref "C73") (pin "2") (pinfunction "2_2") (pintype "passive"))
      (node (ref "C74") (pin "2") (pinfunction "2_2") (pintype "passive"))
      (node (ref "C75") (pin "2") (pinfunction "2_2") (pintype "passive"))
      (node (ref "C76") (pin "2") (pinfunction "2_2") (pintype "passive"))
      (node (ref "C77") (pin "2") (pinfunction "2_2") (pintype "passive"))
      (node (ref "C78") (pin "2") (pinfunction "2_2") (pintype "passive"))
      (node (ref "C79") (pin "2") (pinfunction "2_2") (pintype "passive"))
      (node (ref "C80") (pin "2") (pinfunction "2_2") (pintype "passive"))
      (node (ref "C81") (pin "2") (pinfunction "2_2") (pintype "passive"))
      (node (ref "C82") (pin "2") (pinfunction "2_2") (pintype "passive"))
      (node (ref "C83") (pin "2") (pinfunction "2_2") (pintype "passive"))
      (node (ref "C84") (pin "2") (pinfunction "2_2") (pintype "passive"))
      (node (ref "C85") (pin "2") (pinfunction "2_2") (pintype "passive"))
      (node (ref "C86") (pin "2") (pinfunction "2_2") (pintype "passive"))
      (node (ref "C87") (pin "2") (pinfunction "2_2") (pintype "passive"))
      (node (ref "C88") (pin "2") (pinfunction "2_2") (pintype "passive"))
      (node (ref "C89") (pin "2") (pinfunction "2_2") (pintype "passive"))
      (node (ref "C90") (pin "2") (pinfunction "2_2") (pintype "passive"))
      (node (ref "C91") (pin "2") (pinfunction "2_2") (pintype "passive"))
      (node (ref "C92") (pin "2") (pinfunction "2_2") (pintype "passive"))
      (node (ref "C93") (pin "2") (pinfunction "2_2") (pintype "passive"))
      (node (ref "C94") (pin "2") (pinfunction "2_2") (pintype "passive"))
      (node (ref "C95") (pin "2") (pinfunction "2_2") (pintype "passive"))
      (node (ref "C96") (pin "2") (pinfunction "2_2") (pintype "passive"))
      (node (ref "C97") (pin "2") (pinfunction "2_2") (pintype "passive"))
      (node (ref "C98") (pin "2") (pinfunction "2_2") (pintype "passive"))
      (node (ref "C99") (pin "2") (pinfunction "2_2") (pintype "passive"))
      (node (ref "LED3") (pin "2") (pinfunction "K_2") (pintype "passive"))
      (node (ref "P2") (pin "10") (pinfunction "10_10") (pintype "passive"))
      (node (ref "P2") (pin "11") (pinfunction "11_11") (pintype "passive"))
      (node (ref "P2") (pin "12") (pinfunction "12_12") (pintype "passive"))
      (node (ref "P2") (pin "14") (pinfunction "14_14") (pintype "passive"))
      (node (ref "P2") (pin "16") (pinfunction "16_16") (pintype "passive"))
      (node (ref "P2") (pin "18") (pinfunction "18_18") (pintype "passive"))
      (node (ref "P2") (pin "20") (pinfunction "20_20") (pintype "passive"))
      (node (ref "P2") (pin "4") (pinfunction "4_4") (pintype "passive"))
      (node (ref "P2") (pin "6") (pinfunction "6_6") (pintype "passive"))
      (node (ref "P2") (pin "8") (pinfunction "8_8") (pintype "passive"))
      (node (ref "R37") (pin "1") (pinfunction "1_1") (pintype "passive"))
      (node (ref "R46") (pin "1") (pinfunction "1_1") (pintype "passive"))
      (node (ref "R60") (pin "2") (pinfunction "2_2") (pintype "passive"))
      (node (ref "R63") (pin "1") (pinfunction "1_1") (pintype "passive"))
      (node (ref "R66") (pin "1") (pinfunction "1_1") (pintype "passive"))
      (node (ref "U5") (pin "103") (pinfunction "VSS_103") (pintype "power_in"))
      (node (ref "U5") (pin "120") (pinfunction "VSSC_120") (pintype "power_in"))
      (node (ref "U5") (pin "128") (pinfunction "VSS_128") (pintype "power_in"))
      (node (ref "U5") (pin "13") (pinfunction "VSS_13") (pintype "power_in"))
      (node (ref "U5") (pin "138") (pinfunction "VSSC_138") (pintype "power_in"))
      (node (ref "U5") (pin "149") (pinfunction "VSS_149") (pintype "power_in"))
      (node (ref "U5") (pin "158") (pinfunction "VSSC_158") (pintype "power_in"))
      (node (ref "U5") (pin "168") (pinfunction "VSS_168") (pintype "power_in"))
      (node (ref "U5") (pin "175") (pinfunction "TEST1_175") (pintype "input"))
      (node (ref "U5") (pin "23") (pinfunction "VSS_23") (pintype "power_in"))
      (node (ref "U5") (pin "33") (pinfunction "VSS_33") (pintype "power_in"))
      (node (ref "U5") (pin "45") (pinfunction "VSSC_45") (pintype "power_in"))
      (node (ref "U5") (pin "55") (pinfunction "VSS_55") (pintype "power_in"))
      (node (ref "U5") (pin "70") (pinfunction "VSS_70") (pintype "power_in"))
      (node (ref "U5") (pin "80") (pinfunction "VSS_80") (pintype "power_in"))
      (node (ref "U5") (pin "88") (pinfunction "CLKINSEL_88") (pintype "input"))
      (node (ref "U6") (pin "15") (pinfunction "~{STB}_15") (pintype "input"))
      (node (ref "U6") (pin "8") (pinfunction "GND_8") (pintype "power_in"))
    )
    (net (code "126") (name "Net-(C59-Pad1)") (class "Default")
      (node (ref "C59") (pin "1") (pinfunction "1_1") (pintype "passive"))
      (node (ref "R36") (pin "1") (pinfunction "1_1") (pintype "passive"))
      (node (ref "R37") (pin "2") (pinfunction "2_2") (pintype "passive"))
    )
    (net (code "127") (name "Net-(C60-Pad1)") (class "Default")
      (node (ref "C60") (pin "1") (pinfunction "1_1") (pintype "passive"))
      (node (ref "R44") (pin "1") (pinfunction "1_1") (pintype "passive"))
      (node (ref "R46") (pin "2") (pinfunction "2_2") (pintype "passive"))
    )
    (net (code "128") (name "Net-(D1-k)") (class "Default")
      (node (ref "C61") (pin "1") (pinfunction "1_1") (pintype "passive"))
      (node (ref "C63") (pin "1") (pinfunction "1_1") (pintype "passive"))
      (node (ref "C64") (pin "1") (pinfunction "1_1") (pintype "passive"))
      (node (ref "C65") (pin "1") (pinfunction "1_1") (pintype "passive"))
      (node (ref "D1") (pin "3") (pinfunction "k_3") (pintype "passive"))
      (node (ref "R59") (pin "2") (pinfunction "2_2") (pintype "passive"))
      (node (ref "U5") (pin "91") (pinfunction "VDDA_91") (pintype "power_in"))
    )
    (net (code "129") (name "Net-(LED3-A)") (class "Default")
      (node (ref "LED3") (pin "1") (pinfunction "A_1") (pintype "passive"))
      (node (ref "R58") (pin "2") (pinfunction "2_2") (pintype "passive"))
    )
    (net (code "130") (name "Net-(P2-Pad17)") (class "Default")
      (node (ref "P2") (pin "17") (pinfunction "17_17") (pintype "passive"))
      (node (ref "R66") (pin "2") (pinfunction "2_2") (pintype "passive"))
    )
    (net (code "131") (name "Net-(P2-Pad19)") (class "Default")
      (node (ref "P2") (pin "19") (pinfunction "19_19") (pintype "passive"))
      (node (ref "R67") (pin "2") (pinfunction "2_2") (pintype "passive"))
    )
    (net (code "132") (name "Net-(U5A-CLKIN{slash}UARTCLK)") (class "Default")
      (node (ref "R23") (pin "1") (pinfunction "1_1") (pintype "passive"))
      (node (ref "U5") (pin "98") (pinfunction "CLKIN/UARTCLK_98") (pintype "input"))
    )
    (net (code "133") (name "Net-(U5A-INT6{slash}LCDVD10)") (class "Default")
      (node (ref "R35") (pin "1") (pinfunction "1_1") (pintype "passive"))
      (node (ref "U5") (pin "115") (pinfunction "INT6/LCDVD10_115") (pintype "bidirectional"))
    )
    (net (code "134") (name "Net-(U5A-LCDVD0)") (class "Default")
      (node (ref "R25") (pin "1") (pinfunction "1_1") (pintype "passive"))
      (node (ref "U5") (pin "127") (pinfunction "LCDVD0_127") (pintype "output"))
    )
    (net (code "135") (name "Net-(U5A-LCDVD1)") (class "Default")
      (node (ref "R26") (pin "1") (pinfunction "1_1") (pintype "passive"))
      (node (ref "U5") (pin "126") (pinfunction "LCDVD1_126") (pintype "output"))
    )
    (net (code "136") (name "Net-(U5A-PA3{slash}UARTRX1)") (class "Default")
      (node (ref "R55") (pin "1") (pinfunction "1_1") (pintype "passive"))
      (node (ref "U5") (pin "160") (pinfunction "PA3/UARTRX1_160") (pintype "bidirectional"))
    )
    (net (code "137") (name "Net-(U5A-PA4{slash}UARTTX1)") (class "Default")
      (node (ref "R54") (pin "1") (pinfunction "1_1") (pintype "passive"))
      (node (ref "U5") (pin "159") (pinfunction "PA4/UARTTX1_159") (pintype "bidirectional"))
    )
    (net (code "138") (name "Net-(U5A-PB4{slash}LCDVD12{slash}LCDREV)") (class "Default")
      (node (ref "R53") (pin "1") (pinfunction "1_1") (pintype "passive"))
      (node (ref "U5") (pin "142") (pinfunction "PB4/LCDVD12/LCDREV_142") (pintype "bidirectional"))
    )
    (net (code "139") (name "Net-(U5A-PB5{slash}LCDVD13)") (class "Default")
      (node (ref "R52") (pin "1") (pinfunction "1_1") (pintype "passive"))
      (node (ref "U5") (pin "141") (pinfunction "PB5/LCDVD13_141") (pintype "bidirectional"))
    )
    (net (code "140") (name "Net-(U5A-PB6{slash}LCDVD14)") (class "Default")
      (node (ref "R51") (pin "1") (pinfunction "1_1") (pintype "passive"))
      (node (ref "U5") (pin "140") (pinfunction "PB6/LCDVD14_140") (pintype "bidirectional"))
    )
    (net (code "141") (name "Net-(U5A-PB7{slash}LCDVD15)") (class "Default")
      (node (ref "R50") (pin "1") (pinfunction "1_1") (pintype "passive"))
      (node (ref "U5") (pin "139") (pinfunction "PB7/LCDVD15_139") (pintype "bidirectional"))
    )
    (net (code "142") (name "Net-(U5A-PC0{slash}LCDENAB{slash}LCDSPL)") (class "Default")
      (node (ref "R45") (pin "1") (pinfunction "1_1") (pintype "passive"))
      (node (ref "U5") (pin "137") (pinfunction "PC0/LCDENAB/LCDSPL_137") (pintype "bidirectional"))
    )
    (net (code "143") (name "Net-(U5A-PC1{slash}LCDVDDEN{slash}LCDCLS)") (class "Default")
      (node (ref "R43") (pin "1") (pinfunction "1_1") (pintype "passive"))
      (node (ref "U5") (pin "135") (pinfunction "PC1/LCDVDDEN/LCDCLS_135") (pintype "bidirectional"))
    )
    (net (code "144") (name "Net-(U5A-PC2{slash}LCDDCLKIN)") (class "Default")
      (node (ref "R42") (pin "1") (pinfunction "1_1") (pintype "passive"))
      (node (ref "U5") (pin "134") (pinfunction "PC2/LCDDCLKIN_134") (pintype "bidirectional"))
    )
    (net (code "145") (name "Net-(U5A-PC3{slash}LCDDCLK)") (class "Default")
      (node (ref "R41") (pin "1") (pinfunction "1_1") (pintype "passive"))
      (node (ref "U5") (pin "133") (pinfunction "PC3/LCDDCLK_133") (pintype "bidirectional"))
    )
    (net (code "146") (name "Net-(U5A-PC4{slash}LCDVD16)") (class "Default")
      (node (ref "R49") (pin "1") (pinfunction "1_1") (pintype "passive"))
      (node (ref "U5") (pin "132") (pinfunction "PC4/LCDVD16_132") (pintype "bidirectional"))
    )
    (net (code "147") (name "Net-(U5A-PC5{slash}LCDLP)") (class "Default")
      (node (ref "R40") (pin "1") (pinfunction "1_1") (pintype "passive"))
      (node (ref "U5") (pin "131") (pinfunction "PC5/LCDLP_131") (pintype "bidirectional"))
    )
    (net (code "148") (name "Net-(U5A-PC6{slash}LCDVD17)") (class "Default")
      (node (ref "R48") (pin "1") (pinfunction "1_1") (pintype "passive"))
      (node (ref "U5") (pin "130") (pinfunction "PC6/LCDVD17_130") (pintype "bidirectional"))
    )
    (net (code "149") (name "Net-(U5A-PC7{slash}LCDFP{slash}LCDSPS)") (class "Default")
      (node (ref "R39") (pin "1") (pinfunction "1_1") (pintype "passive"))
      (node (ref "U5") (pin "129") (pinfunction "PC7/LCDFP/LCDSPS_129") (pintype "bidirectional"))
    )
    (net (code "150") (name "Net-(U5A-PD0{slash}LCDVD2)") (class "Default")
      (node (ref "R27") (pin "1") (pinfunction "1_1") (pintype "passive"))
      (node (ref "U5") (pin "124") (pinfunction "PD0/LCDVD2_124") (pintype "bidirectional"))
    )
    (net (code "151") (name "Net-(U5A-PD1{slash}LCDVD3)") (class "Default")
      (node (ref "R28") (pin "1") (pinfunction "1_1") (pintype "passive"))
      (node (ref "U5") (pin "123") (pinfunction "PD1/LCDVD3_123") (pintype "bidirectional"))
    )
    (net (code "152") (name "Net-(U5A-PD2{slash}LCDVD4)") (class "Default")
      (node (ref "R29") (pin "1") (pinfunction "1_1") (pintype "passive"))
      (node (ref "U5") (pin "122") (pinfunction "PD2/LCDVD4_122") (pintype "bidirectional"))
    )
    (net (code "153") (name "Net-(U5A-PD3{slash}LCDVD5)") (class "Default")
      (node (ref "R30") (pin "1") (pinfunction "1_1") (pintype "passive"))
      (node (ref "U5") (pin "121") (pinfunction "PD3/LCDVD5_121") (pintype "bidirectional"))
    )
    (net (code "154") (name "Net-(U5A-PD4{slash}LCDVD6{slash}LCDPS)") (class "Default")
      (node (ref "R31") (pin "1") (pinfunction "1_1") (pintype "passive"))
      (node (ref "U5") (pin "119") (pinfunction "PD4/LCDVD6/LCDPS_119") (pintype "bidirectional"))
    )
    (net (code "155") (name "Net-(U5A-PD5{slash}LCDVD7)") (class "Default")
      (node (ref "R32") (pin "1") (pinfunction "1_1") (pintype "passive"))
      (node (ref "U5") (pin "118") (pinfunction "PD5/LCDVD7_118") (pintype "bidirectional"))
    )
    (net (code "156") (name "Net-(U5A-PD6{slash}LCDVD8)") (class "Default")
      (node (ref "R33") (pin "1") (pinfunction "1_1") (pintype "passive"))
      (node (ref "U5") (pin "117") (pinfunction "PD6/LCDVD8_117") (pintype "bidirectional"))
    )
    (net (code "157") (name "Net-(U5A-PD7{slash}LCDVD9)") (class "Default")
      (node (ref "R34") (pin "1") (pinfunction "1_1") (pintype "passive"))
      (node (ref "U5") (pin "116") (pinfunction "PD7/LCDVD9_116") (pintype "bidirectional"))
    )
    (net (code "158") (name "Net-(U5A-PE6{slash}nDCS1)") (class "Default")
      (node (ref "R21") (pin "1") (pinfunction "1_1") (pintype "passive"))
      (node (ref "U5") (pin "104") (pinfunction "PE6/nDCS1_104") (pintype "bidirectional"))
    )
    (net (code "159") (name "Net-(U5A-PF1{slash}CLKEN)") (class "Default")
      (node (ref "R22") (pin "1") (pinfunction "1_1") (pintype "passive"))
      (node (ref "U5") (pin "99") (pinfunction "PF1/CLKEN_99") (pintype "bidirectional"))
    )
    (net (code "160") (name "Net-(U5A-UARTIRRX0{slash}UARTRX0)") (class "Default")
      (node (ref "R56") (pin "1") (pinfunction "1_1") (pintype "passive"))
      (node (ref "U5") (pin "163") (pinfunction "UARTIRRX0/UARTRX0_163") (pintype "input"))
    )
    (net (code "161") (name "Net-(U5B-VSSA)") (class "Default")
      (node (ref "C61") (pin "2") (pinfunction "2_2") (pintype "passive"))
      (node (ref "C63") (pin "2") (pinfunction "2_2") (pintype "passive"))
      (node (ref "C64") (pin "2") (pinfunction "2_2") (pintype "passive"))
      (node (ref "C65") (pin "2") (pinfunction "2_2") (pintype "passive"))
      (node (ref "U5") (pin "92") (pinfunction "VSSA_92") (pintype "power_in"))
    )
    (net (code "162") (name "Net-(U6-SEL)") (class "Default")
      (node (ref "P1") (pin "1") (pinfunction "1_1") (pintype "passive"))
      (node (ref "R58") (pin "1") (pinfunction "1_1") (pintype "passive"))
      (node (ref "R60") (pin "1") (pinfunction "1_1") (pintype "passive"))
      (node (ref "U6") (pin "1") (pinfunction "SEL_1") (pintype "input"))
    )
    (net (code "163") (name "VCC1V8") (class "Default")
      (node (ref "C100") (pin "1") (pinfunction "1_1") (pintype "passive"))
      (node (ref "C101") (pin "1") (pinfunction "1_1") (pintype "passive"))
      (node (ref "C88") (pin "1") (pinfunction "1_1") (pintype "passive"))
      (node (ref "C89") (pin "1") (pinfunction "1_1") (pintype "passive"))
      (node (ref "C90") (pin "1") (pinfunction "1_1") (pintype "passive"))
      (node (ref "C91") (pin "1") (pinfunction "1_1") (pintype "passive"))
      (node (ref "C92") (pin "1") (pinfunction "1_1") (pintype "passive"))
      (node (ref "C93") (pin "1") (pinfunction "1_1") (pintype "passive"))
      (node (ref "C94") (pin "1") (pinfunction "1_1") (pintype "passive"))
      (node (ref "C95") (pin "1") (pinfunction "1_1") (pintype "passive"))
      (node (ref "C96") (pin "1") (pinfunction "1_1") (pintype "passive"))
      (node (ref "C97") (pin "1") (pinfunction "1_1") (pintype "passive"))
      (node (ref "C98") (pin "1") (pinfunction "1_1") (pintype "passive"))
      (node (ref "C99") (pin "1") (pinfunction "1_1") (pintype "passive"))
      (node (ref "D1") (pin "1") (pinfunction "A_1") (pintype "passive"))
      (node (ref "R59") (pin "1") (pinfunction "1_1") (pintype "passive"))
      (node (ref "U5") (pin "113") (pinfunction "VDDC_113") (pintype "power_in"))
      (node (ref "U5") (pin "136") (pinfunction "VDDC_136") (pintype "power_in"))
      (node (ref "U5") (pin "154") (pinfunction "VDDC_154") (pintype "power_in"))
      (node (ref "U5") (pin "40") (pinfunction "VDDC_40") (pintype "power_in"))
      (node (ref "U5") (pin "75") (pinfunction "VDDC_75") (pintype "power_in"))
      (node (ref "U5") (pin "95") (pinfunction "VDDC_95") (pintype "power_in"))
    )
    (net (code "164") (name "VCC3V3") (class "Default")
      (node (ref "C62") (pin "1") (pinfunction "1_1") (pintype "passive"))
      (node (ref "C66") (pin "1") (pinfunction "1_1") (pintype "passive"))
      (node (ref "C67") (pin "1") (pinfunction "1_1") (pintype "passive"))
      (node (ref "C68") (pin "1") (pinfunction "1_1") (pintype "passive"))
      (node (ref "C69") (pin "1") (pinfunction "1_1") (pintype "passive"))
      (node (ref "C70") (pin "1") (pinfunction "1_1") (pintype "passive"))
      (node (ref "C71") (pin "1") (pinfunction "1_1") (pintype "passive"))
      (node (ref "C72") (pin "1") (pinfunction "1_1") (pintype "passive"))
      (node (ref "C73") (pin "1") (pinfunction "1_1") (pintype "passive"))
      (node (ref "C74") (pin "1") (pinfunction "1_1") (pintype "passive"))
      (node (ref "C75") (pin "1") (pinfunction "1_1") (pintype "passive"))
      (node (ref "C76") (pin "1") (pinfunction "1_1") (pintype "passive"))
      (node (ref "C77") (pin "1") (pinfunction "1_1") (pintype "passive"))
      (node (ref "C78") (pin "1") (pinfunction "1_1") (pintype "passive"))
      (node (ref "C79") (pin "1") (pinfunction "1_1") (pintype "passive"))
      (node (ref "C80") (pin "1") (pinfunction "1_1") (pintype "passive"))
      (node (ref "C81") (pin "1") (pinfunction "1_1") (pintype "passive"))
      (node (ref "C82") (pin "1") (pinfunction "1_1") (pintype "passive"))
      (node (ref "C83") (pin "1") (pinfunction "1_1") (pintype "passive"))
      (node (ref "C84") (pin "1") (pinfunction "1_1") (pintype "passive"))
      (node (ref "C85") (pin "1") (pinfunction "1_1") (pintype "passive"))
      (node (ref "C86") (pin "1") (pinfunction "1_1") (pintype "passive"))
      (node (ref "C87") (pin "1") (pinfunction "1_1") (pintype "passive"))
      (node (ref "P1") (pin "2") (pinfunction "2_2") (pintype "passive"))
      (node (ref "P2") (pin "1") (pinfunction "1_1") (pintype "passive"))
      (node (ref "P2") (pin "2") (pinfunction "2_2") (pintype "passive"))
      (node (ref "R20") (pin "2") (pinfunction "2_2") (pintype "passive"))
      (node (ref "R21") (pin "2") (pinfunction "2_2") (pintype "passive"))
      (node (ref "R22") (pin "2") (pinfunction "2_2") (pintype "passive"))
      (node (ref "R23") (pin "2") (pinfunction "2_2") (pintype "passive"))
      (node (ref "R24") (pin "2") (pinfunction "2_2") (pintype "passive"))
      (node (ref "R25") (pin "2") (pinfunction "2_2") (pintype "passive"))
      (node (ref "R26") (pin "2") (pinfunction "2_2") (pintype "passive"))
      (node (ref "R27") (pin "2") (pinfunction "2_2") (pintype "passive"))
      (node (ref "R28") (pin "2") (pinfunction "2_2") (pintype "passive"))
      (node (ref "R29") (pin "2") (pinfunction "2_2") (pintype "passive"))
      (node (ref "R30") (pin "2") (pinfunction "2_2") (pintype "passive"))
      (node (ref "R31") (pin "2") (pinfunction "2_2") (pintype "passive"))
      (node (ref "R32") (pin "2") (pinfunction "2_2") (pintype "passive"))
      (node (ref "R33") (pin "2") (pinfunction "2_2") (pintype "passive"))
      (node (ref "R34") (pin "2") (pinfunction "2_2") (pintype "passive"))
      (node (ref "R35") (pin "2") (pinfunction "2_2") (pintype "passive"))
      (node (ref "R39") (pin "2") (pinfunction "2_2") (pintype "passive"))
      (node (ref "R40") (pin "2") (pinfunction "2_2") (pintype "passive"))
      (node (ref "R41") (pin "2") (pinfunction "2_2") (pintype "passive"))
      (node (ref "R42") (pin "2") (pinfunction "2_2") (pintype "passive"))
      (node (ref "R43") (pin "2") (pinfunction "2_2") (pintype "passive"))
      (node (ref "R45") (pin "2") (pinfunction "2_2") (pintype "passive"))
      (node (ref "R48") (pin "2") (pinfunction "2_2") (pintype "passive"))
      (node (ref "R49") (pin "2") (pinfunction "2_2") (pintype "passive"))
      (node (ref "R50") (pin "2") (pinfunction "2_2") (pintype "passive"))
      (node (ref "R51") (pin "2") (pinfunction "2_2") (pintype "passive"))
      (node (ref "R52") (pin "2") (pinfunction "2_2") (pintype "passive"))
      (node (ref "R53") (pin "2") (pinfunction "2_2") (pintype "passive"))
      (node (ref "R54") (pin "2") (pinfunction "2_2") (pintype "passive"))
      (node (ref "R55") (pin "2") (pinfunction "2_2") (pintype "passive"))
      (node (ref "R56") (pin "2") (pinfunction "2_2") (pintype "passive"))
      (node (ref "R57") (pin "2") (pinfunction "2_2") (pintype "passive"))
      (node (ref "R61") (pin "1") (pinfunction "1_1") (pintype "passive"))
      (node (ref "R62") (pin "1") (pinfunction "1_1") (pintype "passive"))
      (node (ref "R67") (pin "1") (pinfunction "1_1") (pintype "passive"))
      (node (ref "U5") (pin "1") (pinfunction "nTSTA_1") (pintype "input"))
      (node (ref "U5") (pin "100") (pinfunction "VDD_100") (pintype "power_in"))
      (node (ref "U5") (pin "125") (pinfunction "VDD_125") (pintype "power_in"))
      (node (ref "U5") (pin "143") (pinfunction "VDD_143") (pintype "power_in"))
      (node (ref "U5") (pin "161") (pinfunction "VDD_161") (pintype "power_in"))
      (node (ref "U5") (pin "176") (pinfunction "TEST2_176") (pintype "input"))
      (node (ref "U5") (pin "18") (pinfunction "VDD_18") (pintype "power_in"))
      (node (ref "U5") (pin "28") (pinfunction "VDD_28") (pintype "power_in"))
      (node (ref "U5") (pin "49") (pinfunction "VDD_49") (pintype "power_in"))
      (node (ref "U5") (pin "64") (pinfunction "VDD_64") (pintype "power_in"))
      (node (ref "U5") (pin "8") (pinfunction "VDD_8") (pintype "power_in"))
      (node (ref "U5") (pin "85") (pinfunction "VDD_85") (pintype "power_in"))
      (node (ref "U6") (pin "16") (pinfunction "VDD_16") (pintype "power_in"))
    )
    (net (code "165") (name "unconnected-(D1-Pad2)") (class "Default")
      (node (ref "D1") (pin "2") (pintype "passive"))
    )
    (net (code "166") (name "unconnected-(U5A-CTOUT1B{slash}DACK1-Pad145)") (class "Default")
      (node (ref "U5") (pin "145") (pinfunction "CTOUT1B/DACK1_145") (pintype "output+no_connect"))
    )
    (net (code "167") (name "unconnected-(U5A-PWM1{slash}DEOT1-Pad157)") (class "Default")
      (node (ref "U5") (pin "157") (pinfunction "PWM1/DEOT1_157") (pintype "output+no_connect"))
    )
    (net (code "168") (name "unconnected-(U5A-UARTIRTX0{slash}UARTTX0-Pad162)") (class "Default")
      (node (ref "U5") (pin "162") (pinfunction "UARTIRTX0/UARTTX0_162") (pintype "output"))
    )
  )
)
